# schematic.net
KiCad netlist of a schematic drawn in Altium Designer
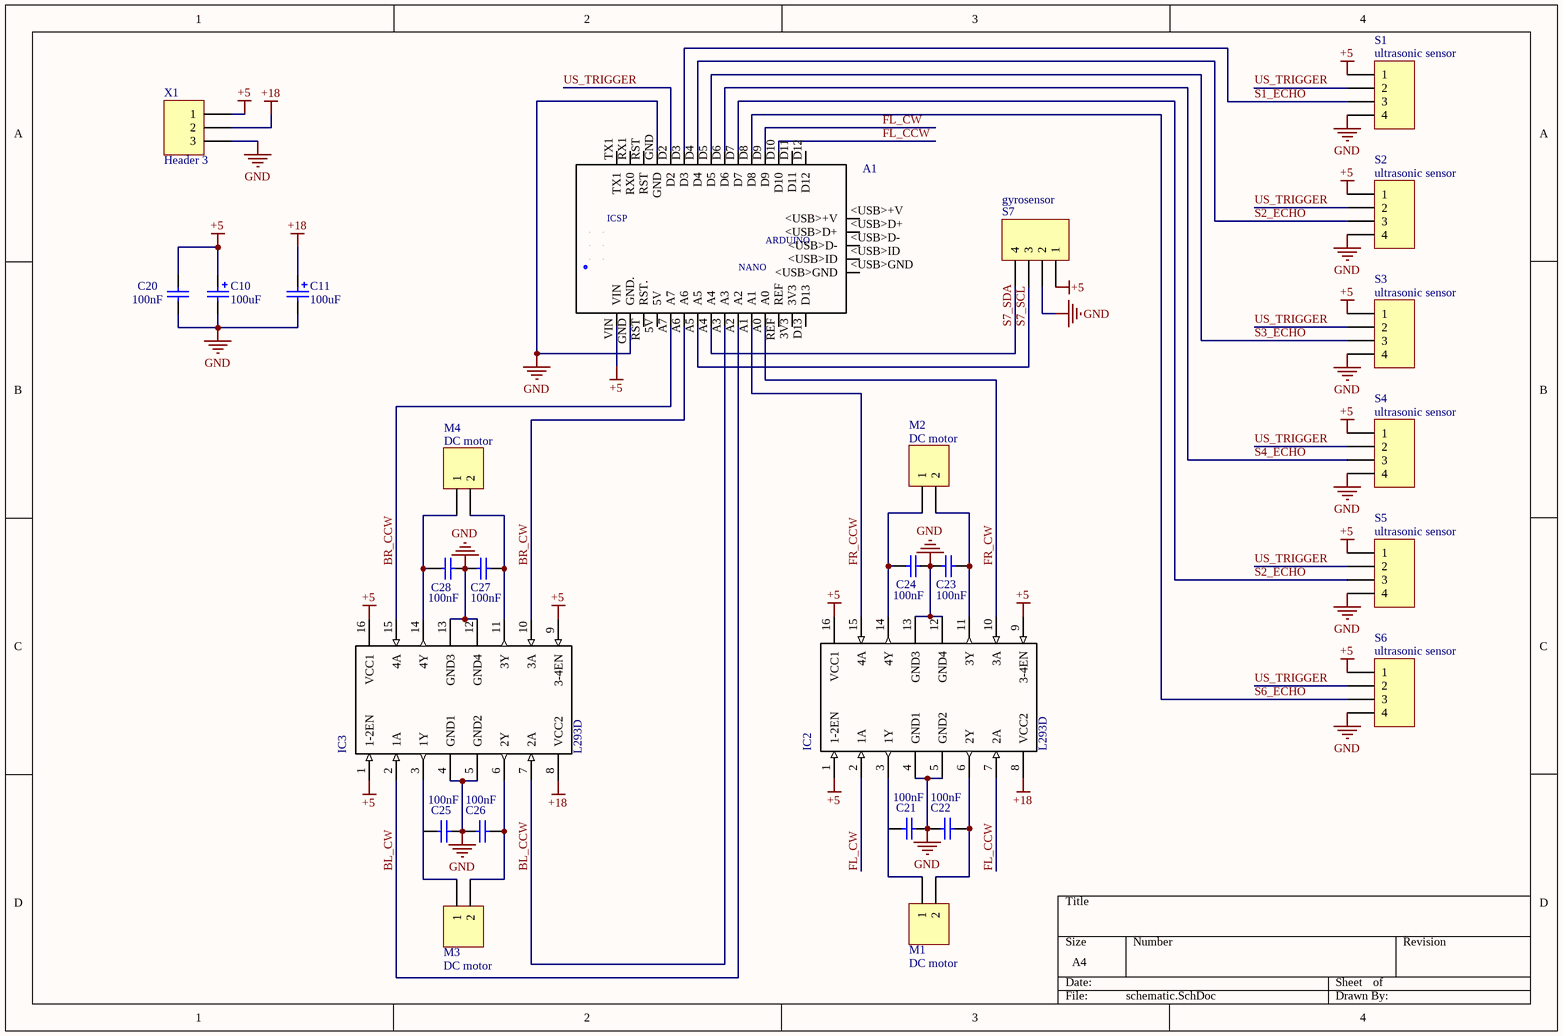
[diagram p0: schematic.SchDoc]

(export (version "E")
  (design (tool "Eeschema 10.0.6"))
  (components
    (comp (ref "A1")
      (value "ARDUINO_NANO")
      (footprint "ARDUINO_NANO:ARDUINO_NANO_ARDUINO_NANO(Primary)")
      (description "Dev.kit: Arduino; UART; ICSP, USB B mini, pin strips")
      (fields (field (name "MP") "ARDUINO NANO") (field (name "MF") "Arduino"))
      (libsource (lib "ARDUINO_NANO") (part "ARDUINO_NANO"))
    )
    (comp (ref "C10")
      (value "100uF")
      (footprint "POLAR0.8")
      (description "Polarized Capacitor (Axial)")
      (fields (field (name "Comment") "Cap Pol2") (field (name "PUBLISHER") "Altium Limited"))
      (libsource (lib "Miscellaneous Devices") (part "Cap Pol2"))
    )
    (comp (ref "C11")
      (value "100uF")
      (footprint "POLAR0.8")
      (description "Polarized Capacitor (Axial)")
      (fields (field (name "Comment") "Cap Pol2") (field (name "PUBLISHER") "Altium Limited"))
      (libsource (lib "Miscellaneous Devices") (part "Cap Pol2"))
    )
    (comp (ref "C20")
      (value "100nF")
      (footprint "RAD-0.3")
      (description "Capacitor")
      (fields (field (name "Comment") "Cap") (field (name "PUBLISHER") "Altium Limited"))
      (libsource (lib "Miscellaneous Devices") (part "Cap"))
    )
    (comp (ref "C21")
      (value "100nF")
      (footprint "RAD-0.3")
      (description "Capacitor")
      (fields (field (name "Comment") "Cap") (field (name "PUBLISHER") "Altium Limited"))
      (libsource (lib "Miscellaneous Devices") (part "Cap"))
    )
    (comp (ref "C22")
      (value "100nF")
      (footprint "RAD-0.3")
      (description "Capacitor")
      (fields (field (name "Comment") "Cap") (field (name "PUBLISHER") "Altium Limited"))
      (libsource (lib "Miscellaneous Devices") (part "Cap"))
    )
    (comp (ref "C23")
      (value "100nF")
      (footprint "RAD-0.3")
      (description "Capacitor")
      (fields (field (name "Comment") "Cap") (field (name "PUBLISHER") "Altium Limited"))
      (libsource (lib "Miscellaneous Devices") (part "Cap"))
    )
    (comp (ref "C24")
      (value "100nF")
      (footprint "RAD-0.3")
      (description "Capacitor")
      (fields (field (name "Comment") "Cap") (field (name "PUBLISHER") "Altium Limited"))
      (libsource (lib "Miscellaneous Devices") (part "Cap"))
    )
    (comp (ref "C25")
      (value "100nF")
      (footprint "RAD-0.3")
      (description "Capacitor")
      (fields (field (name "Comment") "Cap") (field (name "PUBLISHER") "Altium Limited"))
      (libsource (lib "Miscellaneous Devices") (part "Cap"))
    )
    (comp (ref "C26")
      (value "100nF")
      (footprint "RAD-0.3")
      (description "Capacitor")
      (fields (field (name "Comment") "Cap") (field (name "PUBLISHER") "Altium Limited"))
      (libsource (lib "Miscellaneous Devices") (part "Cap"))
    )
    (comp (ref "C27")
      (value "100nF")
      (footprint "RAD-0.3")
      (description "Capacitor")
      (fields (field (name "Comment") "Cap") (field (name "PUBLISHER") "Altium Limited"))
      (libsource (lib "Miscellaneous Devices") (part "Cap"))
    )
    (comp (ref "C28")
      (value "100nF")
      (footprint "RAD-0.3")
      (description "Capacitor")
      (fields (field (name "Comment") "Cap") (field (name "PUBLISHER") "Altium Limited"))
      (libsource (lib "Miscellaneous Devices") (part "Cap"))
    )
    (comp (ref "IC2")
      (value "L293D")
      (footprint "DIL16")
      (description "IC MOTOR DRIVER PAR 16-DIP")
      (fields (field (name "MF") "STMicroelectronics"))
      (libsource (lib "L293D") (part "L293D"))
    )
    (comp (ref "IC3")
      (value "L293D")
      (footprint "DIL16")
      (description "IC MOTOR DRIVER PAR 16-DIP")
      (fields (field (name "MF") "STMicroelectronics"))
      (libsource (lib "L293D") (part "L293D"))
    )
    (comp (ref "M1")
      (value "DC motor")
      (footprint "HDR1X2")
      (description "Header, 2-Pin")
      (fields (field (name "PUBLISHER") "Altium Limited"))
      (libsource (lib "") (part "Header 2_1"))
    )
    (comp (ref "M2")
      (value "DC motor")
      (footprint "HDR1X2")
      (description "Header, 2-Pin")
      (fields (field (name "PUBLISHER") "Altium Limited"))
      (libsource (lib "Miscellaneous Connectors") (part "Header 2"))
    )
    (comp (ref "M3")
      (value "DC motor")
      (footprint "HDR1X2")
      (description "Header, 2-Pin")
      (fields (field (name "PUBLISHER") "Altium Limited"))
      (libsource (lib "") (part "Header 2_1"))
    )
    (comp (ref "M4")
      (value "DC motor")
      (footprint "HDR1X2")
      (description "Header, 2-Pin")
      (fields (field (name "PUBLISHER") "Altium Limited"))
      (libsource (lib "Miscellaneous Connectors") (part "Header 2"))
    )
    (comp (ref "S1")
      (value "ultrasonic sensor")
      (footprint "HDR1X4")
      (description "Header, 4-Pin")
      (fields (field (name "PUBLISHER") "Altium Limited"))
      (libsource (lib "Miscellaneous Connectors") (part "Header 4"))
    )
    (comp (ref "S2")
      (value "ultrasonic sensor")
      (footprint "HDR1X4")
      (description "Header, 4-Pin")
      (fields (field (name "PUBLISHER") "Altium Limited"))
      (libsource (lib "Miscellaneous Connectors") (part "Header 4"))
    )
    (comp (ref "S3")
      (value "ultrasonic sensor")
      (footprint "HDR1X4")
      (description "Header, 4-Pin")
      (fields (field (name "PUBLISHER") "Altium Limited"))
      (libsource (lib "Miscellaneous Connectors") (part "Header 4"))
    )
    (comp (ref "S4")
      (value "ultrasonic sensor")
      (footprint "HDR1X4")
      (description "Header, 4-Pin")
      (fields (field (name "PUBLISHER") "Altium Limited"))
      (libsource (lib "Miscellaneous Connectors") (part "Header 4"))
    )
    (comp (ref "S5")
      (value "ultrasonic sensor")
      (footprint "HDR1X4")
      (description "Header, 4-Pin")
      (fields (field (name "PUBLISHER") "Altium Limited"))
      (libsource (lib "Miscellaneous Connectors") (part "Header 4"))
    )
    (comp (ref "S6")
      (value "ultrasonic sensor")
      (footprint "HDR1X4")
      (description "Header, 4-Pin")
      (fields (field (name "PUBLISHER") "Altium Limited"))
      (libsource (lib "Miscellaneous Connectors") (part "Header 4"))
    )
    (comp (ref "S7")
      (value "gyrosensor")
      (footprint "HDR1X4")
      (description "Header, 4-Pin")
      (fields (field (name "PUBLISHER") "Altium Limited"))
      (libsource (lib "Miscellaneous Connectors") (part "Header 4"))
    )
    (comp (ref "X1")
      (value "Header 3")
      (footprint "HDR1X3")
      (description "Header, 3-Pin")
      (fields (field (name "PUBLISHER") "Altium Limited"))
      (libsource (lib "Miscellaneous Connectors") (part "Header 3"))
    )
  )
  (nets
    (net (code "1") (name "+5") (class "Default")
      (node (ref "A1") (pin "VIN") (pinfunction "VIN_VIN") (pintype "bidirectional"))
      (node (ref "C10") (pin "1") (pinfunction "1_1") (pintype "passive"))
      (node (ref "C20") (pin "1") (pinfunction "1_1") (pintype "passive"))
      (node (ref "IC2") (pin "1") (pinfunction "1-2EN_1") (pintype "input"))
      (node (ref "IC2") (pin "16") (pinfunction "VCC1_16") (pintype "power_in"))
      (node (ref "IC2") (pin "9") (pinfunction "3-4EN_9") (pintype "input"))
      (node (ref "IC3") (pin "1") (pinfunction "1-2EN_1") (pintype "input"))
      (node (ref "IC3") (pin "16") (pinfunction "VCC1_16") (pintype "power_in"))
      (node (ref "IC3") (pin "9") (pinfunction "3-4EN_9") (pintype "input"))
      (node (ref "S1") (pin "1") (pinfunction "1_1") (pintype "passive"))
      (node (ref "S2") (pin "1") (pinfunction "1_1") (pintype "passive"))
      (node (ref "S3") (pin "1") (pinfunction "1_1") (pintype "passive"))
      (node (ref "S4") (pin "1") (pinfunction "1_1") (pintype "passive"))
      (node (ref "S5") (pin "1") (pinfunction "1_1") (pintype "passive"))
      (node (ref "S6") (pin "1") (pinfunction "1_1") (pintype "passive"))
      (node (ref "S7") (pin "1") (pinfunction "1_1") (pintype "passive"))
      (node (ref "X1") (pin "1") (pinfunction "1_1") (pintype "passive"))
    )
    (net (code "2") (name "+18") (class "Default")
      (node (ref "C11") (pin "1") (pinfunction "1_1") (pintype "passive"))
      (node (ref "IC2") (pin "8") (pinfunction "VCC2_8") (pintype "power_in"))
      (node (ref "IC3") (pin "8") (pinfunction "VCC2_8") (pintype "power_in"))
      (node (ref "X1") (pin "2") (pinfunction "2_2") (pintype "passive"))
    )
    (net (code "3") (name "/BL_CCW") (class "Default")
      (node (ref "A1") (pin "A3") (pinfunction "A3_A3") (pintype "bidirectional"))
      (node (ref "IC3") (pin "7") (pinfunction "2A_7") (pintype "input"))
    )
    (net (code "4") (name "/BL_CW") (class "Default")
      (node (ref "A1") (pin "A2") (pinfunction "A2_A2") (pintype "bidirectional"))
      (node (ref "IC3") (pin "2") (pinfunction "1A_2") (pintype "input"))
    )
    (net (code "5") (name "/BR_CCW") (class "Default")
      (node (ref "A1") (pin "A7") (pinfunction "A7_A7") (pintype "bidirectional"))
      (node (ref "IC3") (pin "15") (pinfunction "4A_15") (pintype "input"))
    )
    (net (code "6") (name "/BR_CW") (class "Default")
      (node (ref "A1") (pin "A6") (pinfunction "A6_A6") (pintype "bidirectional"))
      (node (ref "IC3") (pin "10") (pinfunction "3A_10") (pintype "input"))
    )
    (net (code "7") (name "/FL_CCW") (class "Default")
      (node (ref "A1") (pin "D10") (pinfunction "D10_D10") (pintype "bidirectional"))
      (node (ref "IC2") (pin "7") (pinfunction "2A_7") (pintype "input"))
    )
    (net (code "8") (name "/FL_CW") (class "Default")
      (node (ref "A1") (pin "D9") (pinfunction "D9_D9") (pintype "bidirectional"))
      (node (ref "IC2") (pin "2") (pinfunction "1A_2") (pintype "input"))
    )
    (net (code "9") (name "/FR_CCW") (class "Default")
      (node (ref "A1") (pin "A1") (pinfunction "A1_A1") (pintype "bidirectional"))
      (node (ref "IC2") (pin "15") (pinfunction "4A_15") (pintype "input"))
    )
    (net (code "10") (name "/FR_CW") (class "Default")
      (node (ref "A1") (pin "A0") (pinfunction "A0_A0") (pintype "bidirectional"))
      (node (ref "IC2") (pin "10") (pinfunction "3A_10") (pintype "input"))
    )
    (net (code "11") (name "/S1_ECHO") (class "Default")
      (node (ref "A1") (pin "D3") (pinfunction "D3_D3") (pintype "bidirectional"))
      (node (ref "S1") (pin "3") (pinfunction "3_3") (pintype "passive"))
    )
    (net (code "12") (name "/S2_ECHO") (class "Default")
      (node (ref "A1") (pin "D4") (pinfunction "D4_D4") (pintype "bidirectional"))
      (node (ref "A1") (pin "D7") (pinfunction "D7_D7") (pintype "bidirectional"))
      (node (ref "S2") (pin "3") (pinfunction "3_3") (pintype "passive"))
      (node (ref "S5") (pin "3") (pinfunction "3_3") (pintype "passive"))
    )
    (net (code "13") (name "/S3_ECHO") (class "Default")
      (node (ref "A1") (pin "D5") (pinfunction "D5_D5") (pintype "bidirectional"))
      (node (ref "S3") (pin "3") (pinfunction "3_3") (pintype "passive"))
    )
    (net (code "14") (name "/S4_ECHO") (class "Default")
      (node (ref "A1") (pin "D6") (pinfunction "D6_D6") (pintype "bidirectional"))
      (node (ref "S4") (pin "3") (pinfunction "3_3") (pintype "passive"))
    )
    (net (code "15") (name "/S6_ECHO") (class "Default")
      (node (ref "A1") (pin "D8") (pinfunction "D8_D8") (pintype "bidirectional"))
      (node (ref "S6") (pin "3") (pinfunction "3_3") (pintype "passive"))
    )
    (net (code "16") (name "/S7_SCL") (class "Default")
      (node (ref "A1") (pin "A5") (pinfunction "A5_A5") (pintype "bidirectional"))
      (node (ref "S7") (pin "3") (pinfunction "3_3") (pintype "passive"))
    )
    (net (code "17") (name "/S7_SDA") (class "Default")
      (node (ref "A1") (pin "A4") (pinfunction "A4_A4") (pintype "bidirectional"))
      (node (ref "S7") (pin "4") (pinfunction "4_4") (pintype "passive"))
    )
    (net (code "18") (name "/US_TRIGGER") (class "Default")
      (node (ref "A1") (pin "D2") (pinfunction "D2_D2") (pintype "bidirectional"))
      (node (ref "S1") (pin "2") (pinfunction "2_2") (pintype "passive"))
      (node (ref "S2") (pin "2") (pinfunction "2_2") (pintype "passive"))
      (node (ref "S3") (pin "2") (pinfunction "2_2") (pintype "passive"))
      (node (ref "S4") (pin "2") (pinfunction "2_2") (pintype "passive"))
      (node (ref "S5") (pin "2") (pinfunction "2_2") (pintype "passive"))
      (node (ref "S6") (pin "2") (pinfunction "2_2") (pintype "passive"))
    )
    (net (code "19") (name "GND") (class "Default")
      (node (ref "A1") (pin "GND") (pinfunction "GND_GND") (pintype "bidirectional"))
      (node (ref "C10") (pin "2") (pinfunction "2_2") (pintype "passive"))
      (node (ref "C11") (pin "2") (pinfunction "2_2") (pintype "passive"))
      (node (ref "C20") (pin "2") (pinfunction "2_2") (pintype "passive"))
      (node (ref "C21") (pin "2") (pinfunction "2_2") (pintype "passive"))
      (node (ref "C22") (pin "1") (pinfunction "1_1") (pintype "passive"))
      (node (ref "C23") (pin "2") (pinfunction "2_2") (pintype "passive"))
      (node (ref "C24") (pin "1") (pinfunction "1_1") (pintype "passive"))
      (node (ref "C25") (pin "2") (pinfunction "2_2") (pintype "passive"))
      (node (ref "C26") (pin "1") (pinfunction "1_1") (pintype "passive"))
      (node (ref "C27") (pin "2") (pinfunction "2_2") (pintype "passive"))
      (node (ref "C28") (pin "1") (pinfunction "1_1") (pintype "passive"))
      (node (ref "IC2") (pin "12") (pinfunction "GND4_12") (pintype "power_in"))
      (node (ref "IC2") (pin "13") (pinfunction "GND3_13") (pintype "power_in"))
      (node (ref "IC2") (pin "4") (pinfunction "GND1_4") (pintype "power_in"))
      (node (ref "IC2") (pin "5") (pinfunction "GND2_5") (pintype "power_in"))
      (node (ref "IC3") (pin "12") (pinfunction "GND4_12") (pintype "power_in"))
      (node (ref "IC3") (pin "13") (pinfunction "GND3_13") (pintype "power_in"))
      (node (ref "IC3") (pin "4") (pinfunction "GND1_4") (pintype "power_in"))
      (node (ref "IC3") (pin "5") (pinfunction "GND2_5") (pintype "power_in"))
      (node (ref "S1") (pin "4") (pinfunction "4_4") (pintype "passive"))
      (node (ref "S2") (pin "4") (pinfunction "4_4") (pintype "passive"))
      (node (ref "S3") (pin "4") (pinfunction "4_4") (pintype "passive"))
      (node (ref "S4") (pin "4") (pinfunction "4_4") (pintype "passive"))
      (node (ref "S5") (pin "4") (pinfunction "4_4") (pintype "passive"))
      (node (ref "S6") (pin "4") (pinfunction "4_4") (pintype "passive"))
      (node (ref "S7") (pin "2") (pinfunction "2_2") (pintype "passive"))
      (node (ref "X1") (pin "3") (pinfunction "3_3") (pintype "passive"))
    )
    (net (code "20") (name "Net-(IC2-1Y)") (class "Default")
      (node (ref "IC2") (pin "3") (pinfunction "1Y_3") (pintype "output"))
      (node (ref "M1") (pin "1") (pinfunction "1_1") (pintype "passive"))
    )
    (net (code "21") (name "Net-(IC2-2Y)") (class "Default")
      (node (ref "C22") (pin "2") (pinfunction "2_2") (pintype "passive"))
      (node (ref "IC2") (pin "6") (pinfunction "2Y_6") (pintype "output"))
      (node (ref "M1") (pin "2") (pinfunction "2_2") (pintype "passive"))
    )
    (net (code "22") (name "Net-(IC2-3Y)") (class "Default")
      (node (ref "C23") (pin "1") (pinfunction "1_1") (pintype "passive"))
      (node (ref "IC2") (pin "11") (pinfunction "3Y_11") (pintype "output"))
      (node (ref "M2") (pin "2") (pinfunction "2_2") (pintype "passive"))
    )
    (net (code "23") (name "Net-(IC2-4Y)") (class "Default")
      (node (ref "C24") (pin "2") (pinfunction "2_2") (pintype "passive"))
      (node (ref "IC2") (pin "14") (pinfunction "4Y_14") (pintype "output"))
      (node (ref "M2") (pin "1") (pinfunction "1_1") (pintype "passive"))
    )
    (net (code "24") (name "Net-(IC3-1Y)") (class "Default")
      (node (ref "IC3") (pin "3") (pinfunction "1Y_3") (pintype "output"))
      (node (ref "M3") (pin "1") (pinfunction "1_1") (pintype "passive"))
    )
    (net (code "25") (name "Net-(IC3-2Y)") (class "Default")
      (node (ref "C26") (pin "2") (pinfunction "2_2") (pintype "passive"))
      (node (ref "IC3") (pin "6") (pinfunction "2Y_6") (pintype "output"))
      (node (ref "M3") (pin "2") (pinfunction "2_2") (pintype "passive"))
    )
    (net (code "26") (name "Net-(IC3-3Y)") (class "Default")
      (node (ref "C27") (pin "1") (pinfunction "1_1") (pintype "passive"))
      (node (ref "IC3") (pin "11") (pinfunction "3Y_11") (pintype "output"))
      (node (ref "M4") (pin "2") (pinfunction "2_2") (pintype "passive"))
    )
    (net (code "27") (name "Net-(IC3-4Y)") (class "Default")
      (node (ref "C28") (pin "2") (pinfunction "2_2") (pintype "passive"))
      (node (ref "IC3") (pin "14") (pinfunction "4Y_14") (pintype "output"))
      (node (ref "M4") (pin "1") (pinfunction "1_1") (pintype "passive"))
    )
    (net (code "28") (name "unconnected-(A1-5V.-Pad5V)") (class "Default")
      (node (ref "A1") (pin "5V") (pinfunction "5V._5V") (pintype "bidirectional"))
    )
    (net (code "29") (name "unconnected-(A1-Pad3V3)") (class "Default")
      (node (ref "A1") (pin "3V3") (pinfunction "3V3_3V3") (pintype "bidirectional"))
    )
    (net (code "30") (name "unconnected-(A1-Pad5V)") (class "Default")
      (node (ref "A1") (pin "5V") (pinfunction "5V_5V") (pintype "bidirectional"))
    )
    (net (code "31") (name "unconnected-(A1-Pad<USB>+V)") (class "Default")
      (node (ref "A1") (pin "<USB>+V") (pinfunction "<USB>+V_<USB>+V") (pintype "bidirectional"))
    )
    (net (code "32") (name "unconnected-(A1-Pad<USB>D+)") (class "Default")
      (node (ref "A1") (pin "<USB>D+") (pinfunction "<USB>D+_<USB>D+") (pintype "bidirectional"))
    )
    (net (code "33") (name "unconnected-(A1-Pad<USB>D-)") (class "Default")
      (node (ref "A1") (pin "<USB>D-") (pinfunction "<USB>D-_<USB>D-") (pintype "bidirectional"))
    )
    (net (code "34") (name "unconnected-(A1-Pad<USB>GND)") (class "Default")
      (node (ref "A1") (pin "<USB>GND") (pinfunction "<USB>GND_<USB>GND") (pintype "bidirectional"))
    )
    (net (code "35") (name "unconnected-(A1-Pad<USB>ID)") (class "Default")
      (node (ref "A1") (pin "<USB>ID") (pinfunction "<USB>ID_<USB>ID") (pintype "bidirectional"))
    )
    (net (code "36") (name "unconnected-(A1-PadD11)") (class "Default")
      (node (ref "A1") (pin "D11") (pinfunction "D11_D11") (pintype "bidirectional"))
    )
    (net (code "37") (name "unconnected-(A1-PadD12)") (class "Default")
      (node (ref "A1") (pin "D12") (pinfunction "D12_D12") (pintype "bidirectional"))
    )
    (net (code "38") (name "unconnected-(A1-PadD13)") (class "Default")
      (node (ref "A1") (pin "D13") (pinfunction "D13_D13") (pintype "bidirectional"))
    )
    (net (code "39") (name "unconnected-(A1-PadGND_)") (class "Default")
      (node (ref "A1") (pin "GND_") (pinfunction "GND__GND_") (pintype "bidirectional"))
    )
    (net (code "40") (name "unconnected-(A1-PadMISO)") (class "Default")
      (node (ref "A1") (pin "MISO") (pinfunction "MISO_MISO") (pintype "bidirectional"))
    )
    (net (code "41") (name "unconnected-(A1-PadMOSI)") (class "Default")
      (node (ref "A1") (pin "MOSI") (pinfunction "MOSI_MOSI") (pintype "bidirectional"))
    )
    (net (code "42") (name "unconnected-(A1-PadREF)") (class "Default")
      (node (ref "A1") (pin "REF") (pinfunction "REF_REF") (pintype "bidirectional"))
    )
    (net (code "43") (name "unconnected-(A1-PadRST)") (class "Default")
      (node (ref "A1") (pin "RST") (pinfunction "RST_RST") (pintype "bidirectional"))
    )
    (net (code "44") (name "unconnected-(A1-PadSCK)") (class "Default")
      (node (ref "A1") (pin "SCK") (pinfunction "SCK_SCK") (pintype "bidirectional"))
    )
    (net (code "45") (name "unconnected-(A1-PadTX1)") (class "Default")
      (node (ref "A1") (pin "TX1") (pinfunction "TX1_TX1") (pintype "bidirectional"))
    )
    (net (code "46") (name "unconnected-(A1-RESET..-PadRESET)") (class "Default")
      (node (ref "A1") (pin "RESET") (pinfunction "RESET.._RESET") (pintype "bidirectional"))
    )
    (net (code "47") (name "unconnected-(A1-RST.-PadRST)") (class "Default")
      (node (ref "A1") (pin "RST") (pinfunction "RST._RST") (pintype "bidirectional"))
    )
    (net (code "48") (name "unconnected-(A1-RX0-PadRX1)") (class "Default")
      (node (ref "A1") (pin "RX1") (pinfunction "RX0_RX1") (pintype "bidirectional"))
    )
    (net (code "49") (name "unconnected-(C21-Pad1)") (class "Default")
      (node (ref "C21") (pin "1") (pinfunction "1_1") (pintype "passive"))
    )
    (net (code "50") (name "unconnected-(C25-Pad1)") (class "Default")
      (node (ref "C25") (pin "1") (pinfunction "1_1") (pintype "passive"))
    )
  )
)
